# OLED_PCB_Rev1.net
KiCad netlist of a schematic drawn in Altium Designer
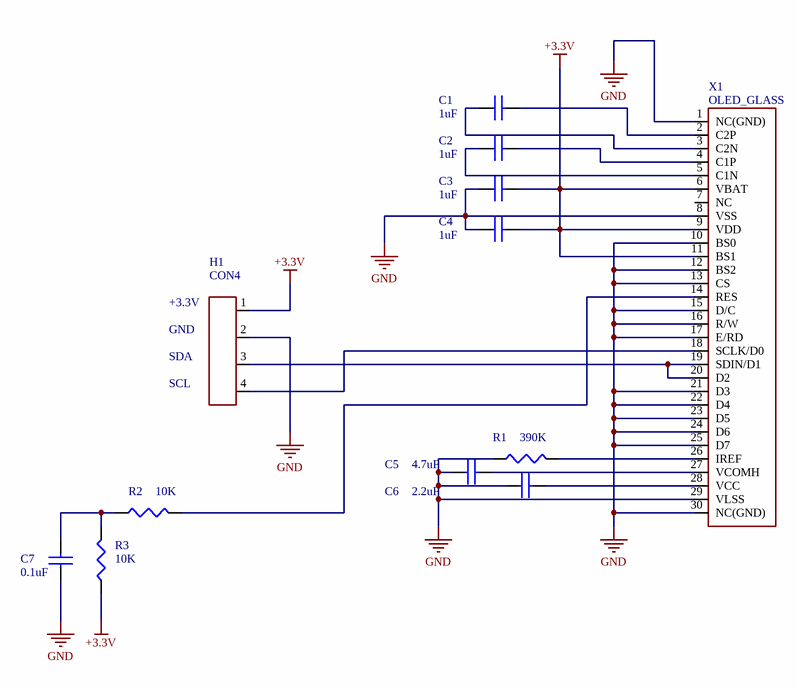
[diagram p0: OLED_PCB_Rev1.SchDoc]

(export (version "E")
  (design (tool "Eeschema 10.0.6"))
  (components
    (comp (ref "C1")
      (value "1uF")
      (footprint "CAPC1608X90N")
      (description "CAP 0603")
      (libsource (lib "Parts_Library") (part "CAP_0603"))
    )
    (comp (ref "C2")
      (value "1uF")
      (footprint "CAPC1608X90N")
      (description "CAP 0603")
      (libsource (lib "Parts_Library") (part "CAP_0603"))
    )
    (comp (ref "C3")
      (value "1uF")
      (footprint "CAPC1608X90N")
      (description "CAP 0603")
      (libsource (lib "Parts_Library") (part "CAP_0603"))
    )
    (comp (ref "C4")
      (value "1uF")
      (footprint "CAPC1608X90N")
      (description "CAP 0603")
      (libsource (lib "Parts_Library") (part "CAP_0603"))
    )
    (comp (ref "C5")
      (value "4.7uF")
      (footprint "CAPC1608X90N")
      (description "CAP 0603")
      (libsource (lib "Parts_Library") (part "CAP_0603"))
    )
    (comp (ref "C6")
      (value "2.2uF")
      (footprint "CAPC1608X90N")
      (description "CAP 0603")
      (libsource (lib "Parts_Library") (part "CAP_0603"))
    )
    (comp (ref "C7")
      (value "0.1uF")
      (footprint "CAPC1608X90N")
      (description "CAP 0603")
      (libsource (lib "Parts_Library") (part "CAP_0603"))
    )
    (comp (ref "H1")
      (value "CON4")
      (footprint "HDR1X4-Empty")
      (description "CONN HEADER 4POS .100\" PADS")
      (fields (field (name "PARTNUMBER") "PADS"))
      (libsource (lib "Parts_Library") (part "CON4"))
    )
    (comp (ref "R1")
      (value "390K")
      (footprint "RESC1608X55N")
      (description "RES 0603")
      (libsource (lib "Parts_Library") (part "RES_0603"))
    )
    (comp (ref "R2")
      (value "10K")
      (footprint "RESC1608X55N")
      (description "RES 0603")
      (libsource (lib "Parts_Library") (part "RES_0603"))
    )
    (comp (ref "R3")
      (value "10K")
      (footprint "RESC1608X55N")
      (description "RES 0603")
      (libsource (lib "Parts_Library") (part "RES_0603"))
    )
    (comp (ref "X1")
      (value "OLED_GLASS")
      (footprint "OLED_GLASS")
      (libsource (lib "Parts_Library") (part "OLED_GLASS"))
    )
  )
  (nets
    (net (code "1") (name "+3.3V") (class "Default")
      (node (ref "C3") (pin "2") (pinfunction "2_2") (pintype "passive"))
      (node (ref "C4") (pin "2") (pinfunction "2_2") (pintype "passive"))
      (node (ref "H1") (pin "1") (pintype "passive"))
      (node (ref "R3") (pin "1") (pinfunction "1_1") (pintype "passive"))
      (node (ref "X1") (pin "11") (pinfunction "BS1_11") (pintype "passive"))
      (node (ref "X1") (pin "6") (pinfunction "VBAT_6") (pintype "passive"))
      (node (ref "X1") (pin "9") (pinfunction "VDD_9") (pintype "passive"))
    )
    (net (code "2") (name "GND") (class "Default")
      (node (ref "C3") (pin "1") (pinfunction "1_1") (pintype "passive"))
      (node (ref "C4") (pin "1") (pinfunction "1_1") (pintype "passive"))
      (node (ref "C5") (pin "1") (pinfunction "1_1") (pintype "passive"))
      (node (ref "C6") (pin "1") (pinfunction "1_1") (pintype "passive"))
      (node (ref "C7") (pin "1") (pinfunction "1_1") (pintype "passive"))
      (node (ref "H1") (pin "2") (pintype "passive"))
      (node (ref "R1") (pin "1") (pinfunction "1_1") (pintype "passive"))
      (node (ref "X1") (pin "1") (pinfunction "NC(GND)_1") (pintype "passive"))
      (node (ref "X1") (pin "10") (pinfunction "BS0_10") (pintype "passive"))
      (node (ref "X1") (pin "12") (pinfunction "BS2_12") (pintype "passive"))
      (node (ref "X1") (pin "13") (pinfunction "CS_13") (pintype "passive"))
      (node (ref "X1") (pin "15") (pinfunction "D/C_15") (pintype "passive"))
      (node (ref "X1") (pin "16") (pinfunction "R/W_16") (pintype "passive"))
      (node (ref "X1") (pin "17") (pinfunction "E/RD_17") (pintype "passive"))
      (node (ref "X1") (pin "21") (pinfunction "D3_21") (pintype "passive"))
      (node (ref "X1") (pin "22") (pinfunction "D4_22") (pintype "passive"))
      (node (ref "X1") (pin "23") (pinfunction "D5_23") (pintype "passive"))
      (node (ref "X1") (pin "24") (pinfunction "D6_24") (pintype "passive"))
      (node (ref "X1") (pin "25") (pinfunction "D7_25") (pintype "passive"))
      (node (ref "X1") (pin "29") (pinfunction "VLSS_29") (pintype "passive"))
      (node (ref "X1") (pin "30") (pinfunction "NC(GND)_30") (pintype "passive"))
      (node (ref "X1") (pin "8") (pinfunction "VSS_8") (pintype "passive"))
    )
    (net (code "3") (name "Net-(C7-Pad2)") (class "Default")
      (node (ref "C7") (pin "2") (pinfunction "2_2") (pintype "passive"))
      (node (ref "R2") (pin "1") (pinfunction "1_1") (pintype "passive"))
      (node (ref "R3") (pin "2") (pinfunction "2_2") (pintype "passive"))
    )
    (net (code "4") (name "Net-(X1-C1N)") (class "Default")
      (node (ref "C2") (pin "1") (pinfunction "1_1") (pintype "passive"))
      (node (ref "X1") (pin "5") (pinfunction "C1N_5") (pintype "passive"))
    )
    (net (code "5") (name "Net-(X1-C1P)") (class "Default")
      (node (ref "C2") (pin "2") (pinfunction "2_2") (pintype "passive"))
      (node (ref "X1") (pin "4") (pinfunction "C1P_4") (pintype "passive"))
    )
    (net (code "6") (name "Net-(X1-C2N)") (class "Default")
      (node (ref "C1") (pin "1") (pinfunction "1_1") (pintype "passive"))
      (node (ref "X1") (pin "3") (pinfunction "C2N_3") (pintype "passive"))
    )
    (net (code "7") (name "Net-(X1-C2P)") (class "Default")
      (node (ref "C1") (pin "2") (pinfunction "2_2") (pintype "passive"))
      (node (ref "X1") (pin "2") (pinfunction "C2P_2") (pintype "passive"))
    )
    (net (code "8") (name "Net-(X1-D2)") (class "Default")
      (node (ref "H1") (pin "3") (pintype "passive"))
      (node (ref "X1") (pin "19") (pinfunction "SDIN/D1_19") (pintype "passive"))
      (node (ref "X1") (pin "20") (pinfunction "D2_20") (pintype "passive"))
    )
    (net (code "9") (name "Net-(X1-IREF)") (class "Default")
      (node (ref "R1") (pin "2") (pinfunction "2_2") (pintype "passive"))
      (node (ref "X1") (pin "26") (pinfunction "IREF_26") (pintype "passive"))
    )
    (net (code "10") (name "Net-(X1-RES)") (class "Default")
      (node (ref "R2") (pin "2") (pinfunction "2_2") (pintype "passive"))
      (node (ref "X1") (pin "14") (pinfunction "RES_14") (pintype "passive"))
    )
    (net (code "11") (name "Net-(X1-SCLK{slash}D0)") (class "Default")
      (node (ref "H1") (pin "4") (pintype "passive"))
      (node (ref "X1") (pin "18") (pinfunction "SCLK/D0_18") (pintype "passive"))
    )
    (net (code "12") (name "Net-(X1-VCC)") (class "Default")
      (node (ref "C6") (pin "2") (pinfunction "2_2") (pintype "passive"))
      (node (ref "X1") (pin "28") (pinfunction "VCC_28") (pintype "passive"))
    )
    (net (code "13") (name "Net-(X1-VCOMH)") (class "Default")
      (node (ref "C5") (pin "2") (pinfunction "2_2") (pintype "passive"))
      (node (ref "X1") (pin "27") (pinfunction "VCOMH_27") (pintype "passive"))
    )
    (net (code "14") (name "unconnected-(X1-NC-Pad7)") (class "Default")
      (node (ref "X1") (pin "7") (pinfunction "NC_7") (pintype "passive"))
    )
  )
)
